# Ultra-Mega-PS-PowerStage-V1_00.net
KiCad netlist of a schematic drawn in Altium Designer
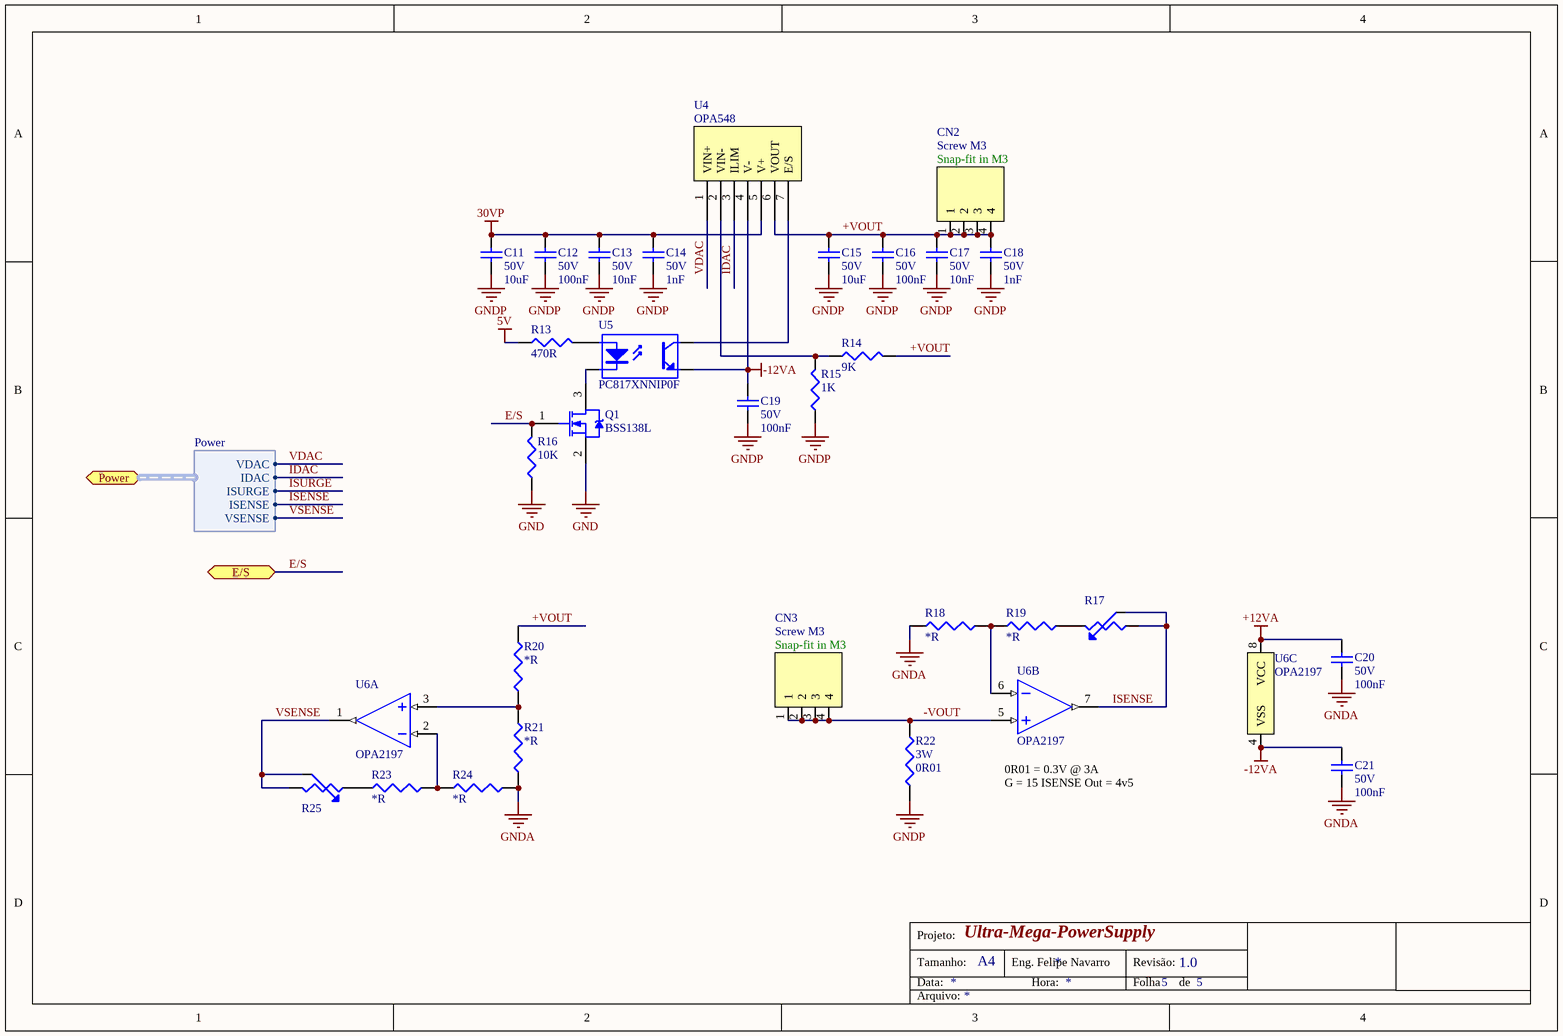
[diagram p0: Ultra-Mega-PS-PowerStage-V1.00.SchDoc]

(export (version "E")
  (design (tool "Eeschema 10.0.6"))
  (components
    (comp (ref "C11")
      (value "10uF")
      (footprint "CC1206")
      (description "Capacitor (Semiconductor SIM Model)")
      (fields (field (name "TENSÃO") "50V") (field (name "Comment") "Capacitor Cerâmico"))
      (libsource (lib "NavarroCAP") (part "Cap 10uF 50V 1206 X5R"))
    )
    (comp (ref "C12")
      (value "100nF")
      (footprint "CC0603")
      (description "Capacitor (Semiconductor SIM Model)")
      (fields (field (name "TENSÃO") "50V") (field (name "Comment") "Capacitor Cerâmico"))
      (libsource (lib "NavarroCAP") (part "Cap 100nF 50V 0603 X7R"))
    )
    (comp (ref "C13")
      (value "10nF")
      (footprint "CC0603")
      (description "Capacitor (Semiconductor SIM Model)")
      (fields (field (name "TENSÃO") "50V") (field (name "Comment") "Capacitor Cerâmico"))
      (libsource (lib "NavarroCAP") (part "Cap 10nF 50V 0603 X7R 5%"))
    )
    (comp (ref "C14")
      (value "1nF")
      (footprint "CC0603")
      (description "Capacitor (Semiconductor SIM Model)")
      (fields (field (name "TENSÃO") "50V") (field (name "Comment") "Capacitor Cerâmico"))
      (libsource (lib "NavarroCAP") (part "Cap 1nF 50V 0603 X7R"))
    )
    (comp (ref "C15")
      (value "10uF")
      (footprint "CC1206")
      (description "Capacitor (Semiconductor SIM Model)")
      (fields (field (name "TENSÃO") "50V") (field (name "Comment") "Capacitor Cerâmico"))
      (libsource (lib "NavarroCAP") (part "Cap 10uF 50V 1206 X5R"))
    )
    (comp (ref "C16")
      (value "100nF")
      (footprint "CC0603")
      (description "Capacitor (Semiconductor SIM Model)")
      (fields (field (name "TENSÃO") "50V") (field (name "Comment") "Capacitor Cerâmico"))
      (libsource (lib "NavarroCAP") (part "Cap 100nF 50V 0603 X7R"))
    )
    (comp (ref "C17")
      (value "10nF")
      (footprint "CC0603")
      (description "Capacitor (Semiconductor SIM Model)")
      (fields (field (name "TENSÃO") "50V") (field (name "Comment") "Capacitor Cerâmico"))
      (libsource (lib "NavarroCAP") (part "Cap 10nF 50V 0603 X7R 5%"))
    )
    (comp (ref "C18")
      (value "1nF")
      (footprint "CC0603")
      (description "Capacitor (Semiconductor SIM Model)")
      (fields (field (name "TENSÃO") "50V") (field (name "Comment") "Capacitor Cerâmico"))
      (libsource (lib "NavarroCAP") (part "Cap 1nF 50V 0603 X7R"))
    )
    (comp (ref "C19")
      (value "100nF")
      (footprint "CC0603")
      (description "Capacitor (Semiconductor SIM Model)")
      (fields (field (name "TENSÃO") "50V") (field (name "Comment") "Capacitor Cerâmico"))
      (libsource (lib "NavarroCAP") (part "Cap 100nF 50V 0603 X7R"))
    )
    (comp (ref "C20")
      (value "100nF")
      (footprint "CC0603")
      (description "Capacitor (Semiconductor SIM Model)")
      (fields (field (name "TENSÃO") "50V") (field (name "Comment") "Capacitor Cerâmico"))
      (libsource (lib "NavarroCAP") (part "Cap 100nF 50V 0603 X7R"))
    )
    (comp (ref "C21")
      (value "100nF")
      (footprint "CC0603")
      (description "Capacitor (Semiconductor SIM Model)")
      (fields (field (name "TENSÃO") "50V") (field (name "Comment") "Capacitor Cerâmico"))
      (libsource (lib "NavarroCAP") (part "Cap 100nF 50V 0603 X7R"))
    )
    (comp (ref "CN2")
      (value "Screw M3")
      (footprint "CONN_MASSA-M3")
      (description "TERM PCB SNAP-IN VERT M3 THREAD")
      (fields (field (name "ALTIUM_VALUE") "Snap-fit in M3"))
      (libsource (lib "NavarroCON") (part "Screw Snap-Fit M3"))
    )
    (comp (ref "CN3")
      (value "Screw M3")
      (footprint "CONN_MASSA-M3")
      (description "TERM PCB SNAP-IN VERT M3 THREAD")
      (fields (field (name "ALTIUM_VALUE") "Snap-fit in M3"))
      (libsource (lib "NavarroCON") (part "Screw Snap-Fit M3"))
    )
    (comp (ref "Q1")
      (value "BSS138L")
      (footprint "SOT-23-3N")
      (description "N-Channel Power MOSFET")
      (libsource (lib "NavarroSEMI") (part "TRS BSS138 50V 200mA SOT-23-3N"))
    )
    (comp (ref "R13")
      (value "470R")
      (footprint "CC0603")
      (description "Resistor")
      (libsource (lib "NavarroRES") (part "Res 470R 5% 0603 1/10W"))
    )
    (comp (ref "R14")
      (value "9K")
      (footprint "CC0603")
      (description "Resistor")
      (libsource (lib "NavarroRES") (part "Res 9K09 1% 0603 1/10W"))
    )
    (comp (ref "R15")
      (value "1K")
      (footprint "CC0603")
      (description "Resistor")
      (libsource (lib "NavarroRES") (part "Res 1K 1% 0603 1/10W"))
    )
    (comp (ref "R16")
      (value "10K")
      (footprint "CC0603")
      (description "Resistor")
      (libsource (lib "NavarroRES") (part "Res 10K 1% 0603 1/10W"))
    )
    (comp (ref "R17")
      (value "Potenciômetro")
      (footprint "POT")
      (description "Trimmer")
      (libsource (lib "NavarroRES") (part "Res Trim"))
    )
    (comp (ref "R18")
      (value "*R")
      (footprint "CC0603")
      (description "Resistor")
      (libsource (lib "NavarroRES") (part "Res - $Val $% $Footprint $Pot"))
    )
    (comp (ref "R19")
      (value "*R")
      (footprint "CC0603")
      (description "Resistor")
      (libsource (lib "NavarroRES") (part "Res - $Val $% $Footprint $Pot"))
    )
    (comp (ref "R20")
      (value "*R")
      (footprint "CC0603")
      (description "Resistor")
      (libsource (lib "NavarroRES") (part "Res - $Val $% $Footprint $Pot"))
    )
    (comp (ref "R21")
      (value "*R")
      (footprint "CC0603")
      (description "Resistor")
      (libsource (lib "NavarroRES") (part "Res - $Val $% $Footprint $Pot"))
    )
    (comp (ref "R22")
      (value "0R01")
      (footprint "CC2512")
      (description "Resistor")
      (fields (field (name "POTÊNCIA") "3W"))
      (libsource (lib "NavarroRES") (part "Res 0R01 1% 2512 3W"))
    )
    (comp (ref "R23")
      (value "*R")
      (footprint "CC0603")
      (description "Resistor")
      (libsource (lib "NavarroRES") (part "Res - $Val $% $Footprint $Pot"))
    )
    (comp (ref "R24")
      (value "*R")
      (footprint "CC0603")
      (description "Resistor")
      (libsource (lib "NavarroRES") (part "Res - $Val $% $Footprint $Pot"))
    )
    (comp (ref "R25")
      (value "Potenciômetro")
      (footprint "POT")
      (description "Trimmer")
      (libsource (lib "NavarroRES") (part "Res Trim"))
    )
    (comp (ref "U4")
      (value "OPA548")
      (footprint "TO-220-7N")
      (description "High-Voltage, High-Current  OPERATIONAL AMPLIFIER")
      (libsource (lib "Navarro") (part "OPA548"))
    )
    (comp (ref "U5")
      (value "PC817XNNIP0F")
      (footprint "SMD-4N")
      (description "4-Pin Phototransistor Optocoupler")
      (libsource (lib "NavarroSEMI") (part "OPT PC817"))
    )
    (comp (ref "U6")
      (value "OPA2197")
      (footprint "SOIC-8N")
      (description "OPAx197 36-V, Precision, Rail-to-Rail Input/Output, Low Offset Voltage, Operational Amplifiers")
      (libsource (lib "") (part "OPA2197_2"))
    )
  )
  (nets
    (net (code "2") (name "+12VA") (class "Default")
      (node (ref "C20") (pin "2") (pinfunction "2_2") (pintype "passive"))
      (node (ref "U6") (pin "8") (pinfunction "VCC_8") (pintype "power_in"))
    )
    (net (code "3") (name "-12VA") (class "Default")
      (node (ref "C19") (pin "2") (pinfunction "2_2") (pintype "passive"))
      (node (ref "C21") (pin "2") (pinfunction "2_2") (pintype "passive"))
      (node (ref "U4") (pin "4") (pinfunction "V-_4") (pintype "power_in"))
      (node (ref "U5") (pin "3") (pinfunction "S_3") (pintype "passive"))
      (node (ref "U6") (pin "4") (pinfunction "VSS_4") (pintype "power_in"))
    )
    (net (code "4") (name "/+VOUT") (class "Default")
      (node (ref "C15") (pin "2") (pinfunction "2_2") (pintype "passive"))
      (node (ref "C16") (pin "2") (pinfunction "2_2") (pintype "passive"))
      (node (ref "C17") (pin "2") (pinfunction "2_2") (pintype "passive"))
      (node (ref "C18") (pin "2") (pinfunction "2_2") (pintype "passive"))
      (node (ref "CN2") (pin "1") (pinfunction "1_1") (pintype "power_in"))
      (node (ref "CN2") (pin "2") (pinfunction "2_2") (pintype "power_in"))
      (node (ref "CN2") (pin "3") (pinfunction "3_3") (pintype "power_in"))
      (node (ref "CN2") (pin "4") (pinfunction "4_4") (pintype "power_in"))
      (node (ref "R14") (pin "1") (pinfunction "1_1") (pintype "passive"))
      (node (ref "R20") (pin "2") (pinfunction "2_2") (pintype "passive"))
      (node (ref "U4") (pin "6") (pinfunction "VOUT_6") (pintype "passive"))
    )
    (net (code "5") (name "/-VOUT") (class "Default")
      (node (ref "CN3") (pin "1") (pinfunction "1_1") (pintype "power_in"))
      (node (ref "CN3") (pin "2") (pinfunction "2_2") (pintype "power_in"))
      (node (ref "CN3") (pin "3") (pinfunction "3_3") (pintype "power_in"))
      (node (ref "CN3") (pin "4") (pinfunction "4_4") (pintype "power_in"))
      (node (ref "R22") (pin "2") (pinfunction "2_2") (pintype "passive"))
      (node (ref "U6") (pin "5") (pinfunction "INB+_5") (pintype "input"))
    )
    (net (code "6") (name "/E{slash}S") (class "Default")
      (node (ref "Q1") (pin "1") (pinfunction "G_1") (pintype "passive"))
      (node (ref "R16") (pin "2") (pinfunction "2_2") (pintype "passive"))
    )
    (net (code "7") (name "/IDAC") (class "Default")
      (node (ref "U4") (pin "3") (pinfunction "ILIM_3") (pintype "passive"))
    )
    (net (code "8") (name "/ISENSE") (class "Default")
      (node (ref "R17") (pin "2") (pinfunction "TAP_2") (pintype "passive"))
      (node (ref "R17") (pin "3") (pinfunction "3_3") (pintype "passive"))
      (node (ref "U6") (pin "7") (pinfunction "OUTB_7") (pintype "output"))
    )
    (net (code "10") (name "/VDAC") (class "Default")
      (node (ref "U4") (pin "1") (pinfunction "VIN+_1") (pintype "passive"))
    )
    (net (code "11") (name "/VSENSE") (class "Default")
      (node (ref "R25") (pin "2") (pinfunction "TAP_2") (pintype "passive"))
      (node (ref "R25") (pin "3") (pinfunction "3_3") (pintype "passive"))
      (node (ref "U6") (pin "1") (pinfunction "OUTA_1") (pintype "output"))
    )
    (net (code "13") (name "5V") (class "Default")
      (node (ref "R13") (pin "1") (pinfunction "1_1") (pintype "passive"))
    )
    (net (code "14") (name "30VP") (class "Default")
      (node (ref "C11") (pin "2") (pinfunction "2_2") (pintype "passive"))
      (node (ref "C12") (pin "2") (pinfunction "2_2") (pintype "passive"))
      (node (ref "C13") (pin "2") (pinfunction "2_2") (pintype "passive"))
      (node (ref "C14") (pin "2") (pinfunction "2_2") (pintype "passive"))
      (node (ref "U4") (pin "5") (pinfunction "V+_5") (pintype "power_in"))
    )
    (net (code "15") (name "GND") (class "Default")
      (node (ref "Q1") (pin "2") (pinfunction "S_2") (pintype "passive"))
      (node (ref "R16") (pin "1") (pinfunction "1_1") (pintype "passive"))
    )
    (net (code "16") (name "GNDA") (class "Default")
      (node (ref "C20") (pin "1") (pinfunction "1_1") (pintype "passive"))
      (node (ref "C21") (pin "1") (pinfunction "1_1") (pintype "passive"))
      (node (ref "R18") (pin "1") (pinfunction "1_1") (pintype "passive"))
      (node (ref "R21") (pin "1") (pinfunction "1_1") (pintype "passive"))
      (node (ref "R24") (pin "2") (pinfunction "2_2") (pintype "passive"))
    )
    (net (code "17") (name "GNDP") (class "Default")
      (node (ref "C11") (pin "1") (pinfunction "1_1") (pintype "passive"))
      (node (ref "C12") (pin "1") (pinfunction "1_1") (pintype "passive"))
      (node (ref "C13") (pin "1") (pinfunction "1_1") (pintype "passive"))
      (node (ref "C14") (pin "1") (pinfunction "1_1") (pintype "passive"))
      (node (ref "C15") (pin "1") (pinfunction "1_1") (pintype "passive"))
      (node (ref "C16") (pin "1") (pinfunction "1_1") (pintype "passive"))
      (node (ref "C17") (pin "1") (pinfunction "1_1") (pintype "passive"))
      (node (ref "C18") (pin "1") (pinfunction "1_1") (pintype "passive"))
      (node (ref "C19") (pin "1") (pinfunction "1_1") (pintype "passive"))
      (node (ref "R15") (pin "1") (pinfunction "1_1") (pintype "passive"))
      (node (ref "R22") (pin "1") (pinfunction "1_1") (pintype "passive"))
    )
    (net (code "18") (name "Net-(Q1-D)") (class "Default")
      (node (ref "Q1") (pin "3") (pinfunction "D_3") (pintype "passive"))
      (node (ref "U5") (pin "2") (pinfunction "K_2") (pintype "passive"))
    )
    (net (code "19") (name "Net-(R17-Pad1)") (class "Default")
      (node (ref "R17") (pin "1") (pinfunction "1_1") (pintype "passive"))
      (node (ref "R19") (pin "2") (pinfunction "2_2") (pintype "passive"))
    )
    (net (code "20") (name "Net-(R23-Pad1)") (class "Default")
      (node (ref "R23") (pin "1") (pinfunction "1_1") (pintype "passive"))
      (node (ref "R25") (pin "1") (pinfunction "1_1") (pintype "passive"))
    )
    (net (code "21") (name "Net-(U4-E{slash}S)") (class "Default")
      (node (ref "U4") (pin "7") (pinfunction "E/S_7") (pintype "passive"))
      (node (ref "U5") (pin "4") (pinfunction "D_4") (pintype "passive"))
    )
    (net (code "22") (name "Net-(U4-VIN-)") (class "Default")
      (node (ref "R14") (pin "2") (pinfunction "2_2") (pintype "passive"))
      (node (ref "R15") (pin "2") (pinfunction "2_2") (pintype "passive"))
      (node (ref "U4") (pin "2") (pinfunction "VIN-_2") (pintype "passive"))
    )
    (net (code "23") (name "Net-(U5-A)") (class "Default")
      (node (ref "R13") (pin "2") (pinfunction "2_2") (pintype "passive"))
      (node (ref "U5") (pin "1") (pinfunction "A_1") (pintype "passive"))
    )
    (net (code "24") (name "Net-(U6A-INA+)") (class "Default")
      (node (ref "R20") (pin "1") (pinfunction "1_1") (pintype "passive"))
      (node (ref "R21") (pin "2") (pinfunction "2_2") (pintype "passive"))
      (node (ref "U6") (pin "3") (pinfunction "INA+_3") (pintype "input"))
    )
    (net (code "25") (name "Net-(U6A-INA-)") (class "Default")
      (node (ref "R23") (pin "2") (pinfunction "2_2") (pintype "passive"))
      (node (ref "R24") (pin "1") (pinfunction "1_1") (pintype "passive"))
      (node (ref "U6") (pin "2") (pinfunction "INA-_2") (pintype "input"))
    )
    (net (code "26") (name "Net-(U6B-INB-)") (class "Default")
      (node (ref "R18") (pin "2") (pinfunction "2_2") (pintype "passive"))
      (node (ref "R19") (pin "1") (pinfunction "1_1") (pintype "passive"))
      (node (ref "U6") (pin "6") (pinfunction "INB-_6") (pintype "input"))
    )
  )
)
